# Buck_5_12.net
KiCad netlist of a schematic drawn in Altium Designer
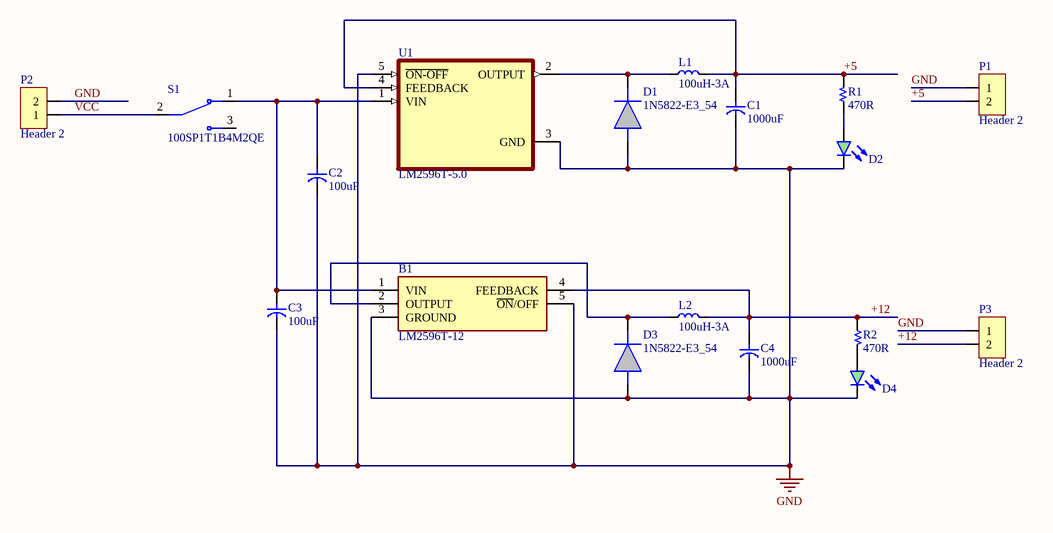
[diagram p0: Buck_5_12.SchDoc]

(export (version "E")
  (design (tool "Eeschema 10.0.6"))
  (components
    (comp (ref "B1")
      (value "LM2596T-12")
      (footprint "TO170P470X1028X2142-5P")
      (description "IC, STEP-DOWN VOLTAGE REGULATOR")
      (fields (field (name "MOUSER PART NUMBER") "926-LM2596T-12"))
      (libsource (lib "LM2596T-12") (part "LM2596T-12"))
    )
    (comp (ref "C1")
      (value "1000uF")
      (footprint "CAP/D80/H125/LS35")
      (description "Capacitor pol")
      (libsource (lib "chipfc_altium_libs") (part "Capacitor"))
    )
    (comp (ref "C2")
      (value "100uF")
      (footprint "CAP/D80/H125/LS35")
      (description "Capacitor pol")
      (libsource (lib "chipfc_altium_libs") (part "Capacitor"))
    )
    (comp (ref "C3")
      (value "100uF")
      (footprint "CAP/D80/H125/LS35")
      (description "Capacitor pol")
      (libsource (lib "chipfc_altium_libs") (part "Capacitor"))
    )
    (comp (ref "C4")
      (value "1000uF")
      (footprint "CAP/D80/H125/LS35")
      (description "Capacitor pol")
      (libsource (lib "chipfc_altium_libs") (part "Capacitor"))
    )
    (comp (ref "D1")
      (value "1N5822-E3_54")
      (footprint "DIOAD2855W132L835D505")
      (description "VISHAY - 1N5822-E3/54 - Schottky Rectifier, 40 V, 3 A, Single, DO-201AD, 2 Pins, 525 mV")
      (fields
        (field (name "MANUFACTURER_PART_NUMBER") "1N5822-E3/54")
        (field (name "MOUSER PART NUMBER") "625-1N5822-E3")
      )
      (libsource (lib "1N5822-E3_54") (part "1N5822-E3_54"))
    )
    (comp (ref "D2")
      (value "LED GREEN")
      (footprint "LED 10MM - GREEN")
      (description "Typical LED 3-pin 2-color")
      (libsource (lib "chipfc_altium_libs") (part "LED GREEN"))
    )
    (comp (ref "D3")
      (value "1N5822-E3_54")
      (footprint "DIOAD2855W132L835D505")
      (description "VISHAY - 1N5822-E3/54 - Schottky Rectifier, 40 V, 3 A, Single, DO-201AD, 2 Pins, 525 mV")
      (fields
        (field (name "MANUFACTURER_PART_NUMBER") "1N5822-E3/54")
        (field (name "MOUSER PART NUMBER") "625-1N5822-E3")
      )
      (libsource (lib "1N5822-E3_54") (part "1N5822-E3_54"))
    )
    (comp (ref "D4")
      (value "LED GREEN")
      (footprint "LED 10MM - GREEN")
      (description "Typical LED 3-pin 2-color")
      (libsource (lib "chipfc_altium_libs") (part "LED GREEN"))
    )
    (comp (ref "L1")
      (value "100uH-3A")
      (footprint "R 1/4W")
      (description "Inductor")
      (libsource (lib "chipfc_altium_libs") (part "Inductor"))
    )
    (comp (ref "L2")
      (value "100uH-3A")
      (footprint "R 1/4W")
      (description "Inductor")
      (libsource (lib "chipfc_altium_libs") (part "Inductor"))
    )
    (comp (ref "P1")
      (value "Header 2")
      (footprint "HDR/Terminal/2")
      (description "Header, 2-Pin")
      (libsource (lib "") (part "Header 2_1"))
    )
    (comp (ref "P2")
      (value "Header 2")
      (footprint "HDR/Terminal/2")
      (description "Header, 2-Pin")
      (libsource (lib "chipfc_altium_libs") (part "Header 2"))
    )
    (comp (ref "P3")
      (value "Header 2")
      (footprint "HDR/Terminal/2")
      (description "Header, 2-Pin")
      (libsource (lib "") (part "Header 2_1"))
    )
    (comp (ref "R1")
      (value "470R")
      (footprint "R 1/4W/300")
      (description "Resistor")
      (libsource (lib "chipfc_altium_libs") (part "Resistor"))
    )
    (comp (ref "R2")
      (value "470R")
      (footprint "R 1/4W/300")
      (description "Resistor")
      (libsource (lib "chipfc_altium_libs") (part "Resistor"))
    )
    (comp (ref "S1")
      (value "100SP1T1B4M2QE")
      (footprint "SW_100SP1T1B4M2QE")
      (description "Toggle Switch SPDT Through Hole")
      (libsource (lib "100SP1T1B4M2QE") (part "100SP1T1B4M2QE"))
    )
    (comp (ref "U1")
      (value "LM2596T-5.0")
      (footprint "TO170P1016X470X2092-5")
      (description "SIMPLE SWITCHERÂ® 4.5V to 40V, 3A Low Component Count Step-Down Regulator 5-TO-220")
      (fields (field (name "MF") "Texas Instruments"))
      (libsource (lib "LM2596T-5.0") (part "LM2596T-5.0"))
    )
  )
  (nets
    (net (code "1") (name "/+5") (class "Default")
      (node (ref "C1") (pin "1") (pinfunction "1_1") (pintype "passive"))
      (node (ref "L1") (pin "2") (pinfunction "2_2") (pintype "passive"))
      (node (ref "P1") (pin "2") (pinfunction "2_2") (pintype "passive"))
      (node (ref "R1") (pin "2") (pinfunction "2_2") (pintype "passive"))
      (node (ref "U1") (pin "4") (pinfunction "FEEDBACK_4") (pintype "input"))
    )
    (net (code "2") (name "/+12") (class "Default")
      (node (ref "B1") (pin "4") (pinfunction "FEEDBACK_4") (pintype "passive"))
      (node (ref "C4") (pin "1") (pinfunction "1_1") (pintype "passive"))
      (node (ref "L2") (pin "2") (pinfunction "2_2") (pintype "passive"))
      (node (ref "P3") (pin "2") (pinfunction "2_2") (pintype "passive"))
      (node (ref "R2") (pin "1") (pinfunction "1_1") (pintype "passive"))
    )
    (net (code "3") (name "/VCC") (class "Default")
      (node (ref "P2") (pin "1") (pinfunction "1_1") (pintype "passive"))
      (node (ref "S1") (pin "2") (pinfunction "2_2") (pintype "passive"))
    )
    (net (code "4") (name "GND") (class "Default")
      (node (ref "B1") (pin "3") (pinfunction "GROUND_3") (pintype "passive"))
      (node (ref "B1") (pin "5") (pinfunction "~{ON}/OFF_5") (pintype "passive"))
      (node (ref "C1") (pin "2") (pinfunction "2_2") (pintype "passive"))
      (node (ref "C2") (pin "2") (pinfunction "2_2") (pintype "passive"))
      (node (ref "C3") (pin "2") (pinfunction "2_2") (pintype "passive"))
      (node (ref "C4") (pin "2") (pinfunction "2_2") (pintype "passive"))
      (node (ref "D1") (pin "1") (pinfunction "A_1") (pintype "passive"))
      (node (ref "D2") (pin "2") (pinfunction "K_2") (pintype "passive"))
      (node (ref "D3") (pin "1") (pinfunction "A_1") (pintype "passive"))
      (node (ref "D4") (pin "2") (pinfunction "K_2") (pintype "passive"))
      (node (ref "P1") (pin "1") (pinfunction "1_1") (pintype "passive"))
      (node (ref "P2") (pin "2") (pinfunction "2_2") (pintype "passive"))
      (node (ref "P3") (pin "1") (pinfunction "1_1") (pintype "passive"))
      (node (ref "U1") (pin "3") (pinfunction "GND_3") (pintype "power_in"))
      (node (ref "U1") (pin "5") (pinfunction "~{ON-OFF}_5") (pintype "input"))
    )
    (net (code "5") (name "Net-(B1-OUTPUT)") (class "Default")
      (node (ref "B1") (pin "2") (pinfunction "OUTPUT_2") (pintype "passive"))
      (node (ref "D3") (pin "2") (pinfunction "K_2") (pintype "passive"))
      (node (ref "L2") (pin "1") (pinfunction "1_1") (pintype "passive"))
    )
    (net (code "6") (name "Net-(B1-VIN)") (class "Default")
      (node (ref "B1") (pin "1") (pinfunction "VIN_1") (pintype "passive"))
      (node (ref "C2") (pin "1") (pinfunction "1_1") (pintype "passive"))
      (node (ref "C3") (pin "1") (pinfunction "1_1") (pintype "passive"))
      (node (ref "S1") (pin "1") (pinfunction "1_1") (pintype "passive"))
      (node (ref "U1") (pin "1") (pinfunction "VIN_1") (pintype "input"))
    )
    (net (code "7") (name "Net-(D1-K)") (class "Default")
      (node (ref "D1") (pin "2") (pinfunction "K_2") (pintype "passive"))
      (node (ref "L1") (pin "1") (pinfunction "1_1") (pintype "passive"))
      (node (ref "U1") (pin "2") (pinfunction "OUTPUT_2") (pintype "output"))
    )
    (net (code "8") (name "Net-(D2-A)") (class "Default")
      (node (ref "D2") (pin "1") (pinfunction "A_1") (pintype "passive"))
      (node (ref "R1") (pin "1") (pinfunction "1_1") (pintype "passive"))
    )
    (net (code "9") (name "Net-(D4-A)") (class "Default")
      (node (ref "D4") (pin "1") (pinfunction "A_1") (pintype "passive"))
      (node (ref "R2") (pin "2") (pinfunction "2_2") (pintype "passive"))
    )
    (net (code "10") (name "unconnected-(S1-Pad3)") (class "Default")
      (node (ref "S1") (pin "3") (pinfunction "3_3") (pintype "passive"))
    )
  )
)
